# CPU.net
KiCad netlist of a schematic drawn in Altium Designer
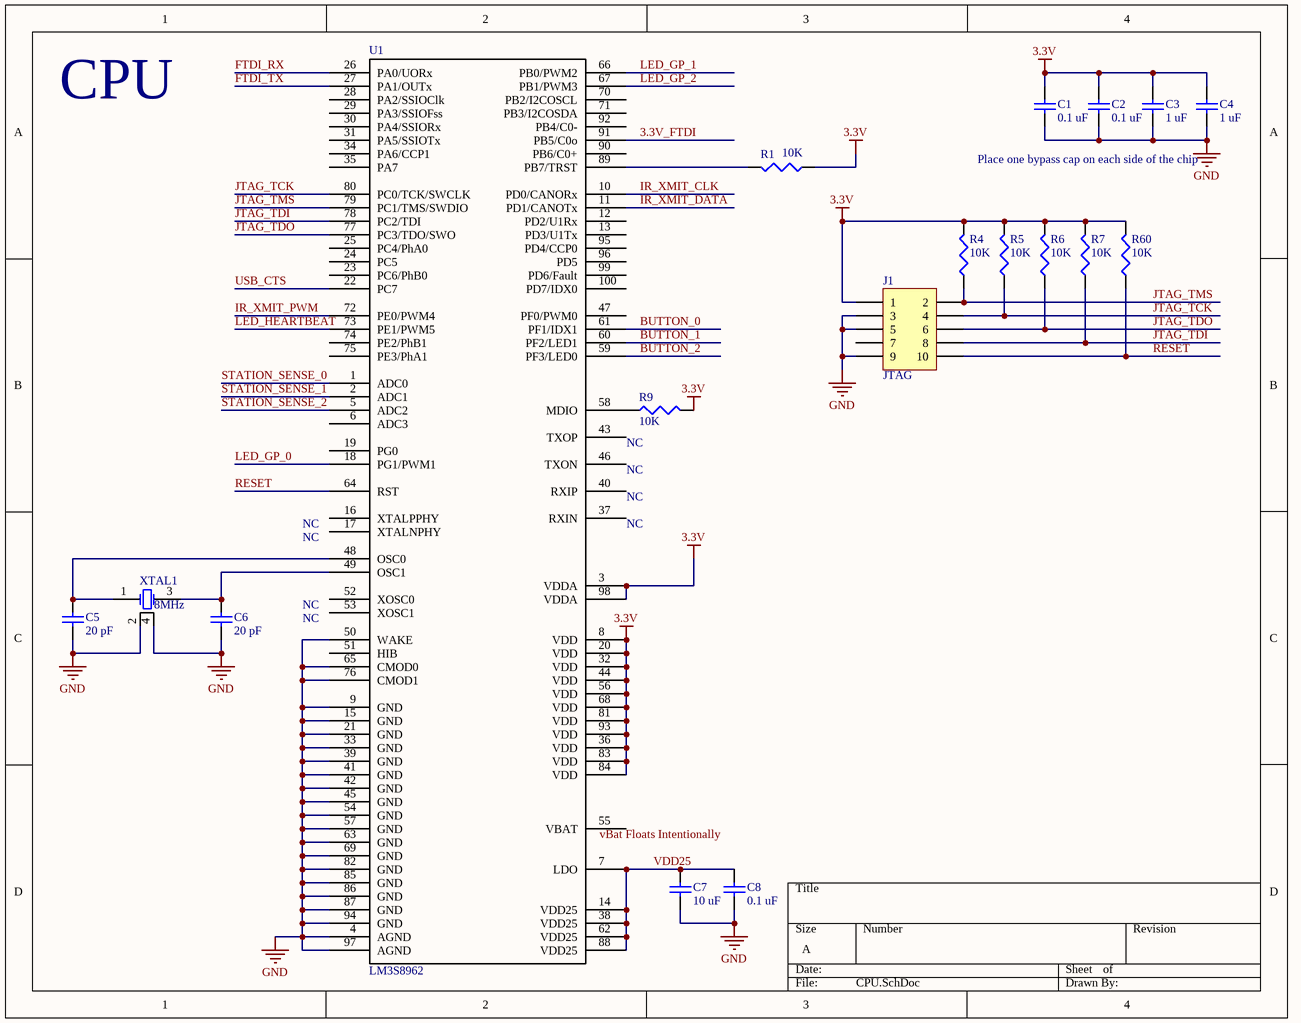
[diagram p0: CPU.SchDoc]

(export (version "E")
  (design (tool "Eeschema 10.0.6"))
  (components
    (comp (ref "C1")
      (value "0.1 uF")
      (footprint "CAPC1005L")
      (description "Capacitor")
      (fields (field (name "PUBLISHER") "Altium Limited"))
      (libsource (lib "mrone") (part "Cap"))
    )
    (comp (ref "C2")
      (value "0.1 uF")
      (footprint "CAPC1005L")
      (description "Capacitor")
      (fields (field (name "PUBLISHER") "Altium Limited"))
      (libsource (lib "mrone") (part "Cap"))
    )
    (comp (ref "C3")
      (value "1 uF")
      (footprint "CAPC1608L")
      (description "Capacitor")
      (fields (field (name "PUBLISHER") "Altium Limited"))
      (libsource (lib "mrone") (part "Cap"))
    )
    (comp (ref "C4")
      (value "1 uF")
      (footprint "CAPC1608L")
      (description "Capacitor")
      (fields (field (name "PUBLISHER") "Altium Limited"))
      (libsource (lib "mrone") (part "Cap"))
    )
    (comp (ref "C5")
      (value "20 pF")
      (footprint "CAPC1005L")
      (description "Capacitor")
      (fields (field (name "PUBLISHER") "Altium Limited"))
      (libsource (lib "mrone") (part "Cap"))
    )
    (comp (ref "C6")
      (value "20 pF")
      (footprint "CAPC1005L")
      (description "Capacitor")
      (fields (field (name "PUBLISHER") "Altium Limited"))
      (libsource (lib "mrone") (part "Cap"))
    )
    (comp (ref "C7")
      (value "10 uF")
      (footprint "CAPC1608L")
      (description "Capacitor")
      (fields (field (name "PUBLISHER") "Altium Limited"))
      (libsource (lib "mrone") (part "Cap"))
    )
    (comp (ref "C8")
      (value "0.1 uF")
      (footprint "CAPC1005L")
      (description "Capacitor")
      (fields (field (name "PUBLISHER") "Altium Limited"))
      (libsource (lib "mrone") (part "Cap"))
    )
    (comp (ref "J1")
      (value "JTAG")
      (footprint "JTAG-10")
      (description "Header, 5-Pin, Dual row, Right Angle")
      (fields (field (name "PUBLISHER") "Altium Limited"))
      (libsource (lib "Miscellaneous Connectors") (part "Header 5X2H"))
    )
    (comp (ref "R1")
      (value "10K")
      (footprint "RESC1608L")
      (description "Resistor")
      (fields (field (name "Comment") "Res3") (field (name "PUBLISHER") "Altium Limited"))
      (libsource (lib "Miscellaneous Devices") (part "Res3"))
    )
    (comp (ref "R4")
      (value "10K")
      (footprint "RESC1608L")
      (description "Resistor")
      (fields (field (name "Comment") "Res3") (field (name "PUBLISHER") "Altium Limited"))
      (libsource (lib "Miscellaneous Devices") (part "Res3"))
    )
    (comp (ref "R5")
      (value "10K")
      (footprint "RESC1608L")
      (description "Resistor")
      (fields (field (name "Comment") "Res3") (field (name "PUBLISHER") "Altium Limited"))
      (libsource (lib "Miscellaneous Devices") (part "Res3"))
    )
    (comp (ref "R6")
      (value "10K")
      (footprint "RESC1608L")
      (description "Resistor")
      (fields (field (name "Comment") "Res3") (field (name "PUBLISHER") "Altium Limited"))
      (libsource (lib "Miscellaneous Devices") (part "Res3"))
    )
    (comp (ref "R7")
      (value "10K")
      (footprint "RESC1608L")
      (description "Resistor")
      (fields (field (name "Comment") "Res3") (field (name "PUBLISHER") "Altium Limited"))
      (libsource (lib "Miscellaneous Devices") (part "Res3"))
    )
    (comp (ref "R9")
      (value "10K")
      (footprint "RESC1608L")
      (description "Resistor")
      (fields (field (name "Comment") "Res3") (field (name "PUBLISHER") "Altium Limited"))
      (libsource (lib "Miscellaneous Devices") (part "Res3"))
    )
    (comp (ref "R60")
      (value "10K")
      (footprint "RESC1608L")
      (description "Resistor")
      (fields (field (name "Comment") "Res3") (field (name "PUBLISHER") "Altium Limited"))
      (libsource (lib "Miscellaneous Devices") (part "Res3"))
    )
    (comp (ref "U1")
      (value "LM3S8962")
      (footprint "LQFP-100")
      (libsource (lib "Schematic Components") (part "LM3S8962"))
    )
    (comp (ref "XTAL1") (value "8MHz") (footprint "CRYSTAL") (libsource (lib "mrone") (part "Crystal")))
  )
  (nets
    (net (code "1") (name "/3.3V_FTDI") (class "Default")
      (node (ref "U1") (pin "91") (pinfunction "PB5/C0o_91") (pintype "passive"))
    )
    (net (code "2") (name "/BUTTON_0") (class "Default")
      (node (ref "U1") (pin "61") (pinfunction "PF1/IDX1_61") (pintype "passive"))
    )
    (net (code "3") (name "/BUTTON_1") (class "Default")
      (node (ref "U1") (pin "60") (pinfunction "PF2/LED1_60") (pintype "passive"))
    )
    (net (code "4") (name "/BUTTON_2") (class "Default")
      (node (ref "U1") (pin "59") (pinfunction "PF3/LED0_59") (pintype "passive"))
    )
    (net (code "5") (name "/FTDI_RX") (class "Default")
      (node (ref "U1") (pin "26") (pinfunction "PA0/UORx_26") (pintype "passive"))
    )
    (net (code "6") (name "/FTDI_TX") (class "Default")
      (node (ref "U1") (pin "27") (pinfunction "PA1/OUTx_27") (pintype "passive"))
    )
    (net (code "7") (name "/IR_XMIT_CLK") (class "Default")
      (node (ref "U1") (pin "10") (pinfunction "PD0/CANORx_10") (pintype "passive"))
    )
    (net (code "8") (name "/IR_XMIT_DATA") (class "Default")
      (node (ref "U1") (pin "11") (pinfunction "PD1/CANOTx_11") (pintype "passive"))
    )
    (net (code "9") (name "/IR_XMIT_PWM") (class "Default")
      (node (ref "U1") (pin "72") (pinfunction "PE0/PWM4_72") (pintype "passive"))
    )
    (net (code "10") (name "/JTAG_TCK") (class "Default")
      (node (ref "J1") (pin "4") (pinfunction "4_4") (pintype "passive"))
      (node (ref "R5") (pin "1") (pinfunction "1_1") (pintype "passive"))
      (node (ref "U1") (pin "80") (pinfunction "PC0/TCK/SWCLK_80") (pintype "passive"))
    )
    (net (code "11") (name "/JTAG_TDI") (class "Default")
      (node (ref "J1") (pin "8") (pinfunction "8_8") (pintype "passive"))
      (node (ref "R7") (pin "1") (pinfunction "1_1") (pintype "passive"))
      (node (ref "U1") (pin "78") (pinfunction "PC2/TDI_78") (pintype "passive"))
    )
    (net (code "12") (name "/JTAG_TDO") (class "Default")
      (node (ref "J1") (pin "6") (pinfunction "6_6") (pintype "passive"))
      (node (ref "R6") (pin "1") (pinfunction "1_1") (pintype "passive"))
      (node (ref "U1") (pin "77") (pinfunction "PC3/TDO/SWO_77") (pintype "passive"))
    )
    (net (code "13") (name "/JTAG_TMS") (class "Default")
      (node (ref "J1") (pin "2") (pinfunction "2_2") (pintype "passive"))
      (node (ref "R4") (pin "1") (pinfunction "1_1") (pintype "passive"))
      (node (ref "U1") (pin "79") (pinfunction "PC1/TMS/SWDIO_79") (pintype "passive"))
    )
    (net (code "14") (name "/LED_GP_0") (class "Default")
      (node (ref "U1") (pin "18") (pinfunction "PG1/PWM1_18") (pintype "passive"))
    )
    (net (code "15") (name "/LED_GP_1") (class "Default")
      (node (ref "U1") (pin "66") (pinfunction "PB0/PWM2_66") (pintype "passive"))
    )
    (net (code "16") (name "/LED_GP_2") (class "Default")
      (node (ref "U1") (pin "67") (pinfunction "PB1/PWM3_67") (pintype "passive"))
    )
    (net (code "17") (name "/LED_HEARTBEAT") (class "Default")
      (node (ref "U1") (pin "73") (pinfunction "PE1/PWM5_73") (pintype "passive"))
    )
    (net (code "18") (name "/RESET") (class "Default")
      (node (ref "J1") (pin "10") (pinfunction "10_10") (pintype "passive"))
      (node (ref "R60") (pin "1") (pinfunction "1_1") (pintype "passive"))
      (node (ref "U1") (pin "64") (pinfunction "RST_64") (pintype "passive"))
    )
    (net (code "19") (name "/STATION_SENSE_0") (class "Default")
      (node (ref "U1") (pin "1") (pinfunction "ADC0_1") (pintype "passive"))
    )
    (net (code "20") (name "/STATION_SENSE_1") (class "Default")
      (node (ref "U1") (pin "2") (pinfunction "ADC1_2") (pintype "passive"))
    )
    (net (code "21") (name "/STATION_SENSE_2") (class "Default")
      (node (ref "U1") (pin "5") (pinfunction "ADC2_5") (pintype "passive"))
    )
    (net (code "22") (name "/USB_CTS") (class "Default")
      (node (ref "U1") (pin "22") (pinfunction "PC7_22") (pintype "passive"))
    )
    (net (code "23") (name "/VDD25") (class "Default")
      (node (ref "C7") (pin "2") (pinfunction "2_2") (pintype "passive"))
      (node (ref "C8") (pin "2") (pinfunction "2_2") (pintype "passive"))
      (node (ref "U1") (pin "14") (pinfunction "VDD25_14") (pintype "passive"))
      (node (ref "U1") (pin "38") (pinfunction "VDD25_38") (pintype "passive"))
      (node (ref "U1") (pin "62") (pinfunction "VDD25_62") (pintype "passive"))
      (node (ref "U1") (pin "7") (pinfunction "LDO_7") (pintype "passive"))
      (node (ref "U1") (pin "88") (pinfunction "VDD25_88") (pintype "passive"))
    )
    (net (code "24") (name "3.3V") (class "Default")
      (node (ref "C1") (pin "2") (pinfunction "2_2") (pintype "passive"))
      (node (ref "C2") (pin "2") (pinfunction "2_2") (pintype "passive"))
      (node (ref "C3") (pin "2") (pinfunction "2_2") (pintype "passive"))
      (node (ref "C4") (pin "2") (pinfunction "2_2") (pintype "passive"))
      (node (ref "J1") (pin "1") (pinfunction "1_1") (pintype "passive"))
      (node (ref "R1") (pin "1") (pinfunction "1_1") (pintype "passive"))
      (node (ref "R4") (pin "2") (pinfunction "2_2") (pintype "passive"))
      (node (ref "R5") (pin "2") (pinfunction "2_2") (pintype "passive"))
      (node (ref "R6") (pin "2") (pinfunction "2_2") (pintype "passive"))
      (node (ref "R60") (pin "2") (pinfunction "2_2") (pintype "passive"))
      (node (ref "R7") (pin "2") (pinfunction "2_2") (pintype "passive"))
      (node (ref "R9") (pin "2") (pinfunction "2_2") (pintype "passive"))
      (node (ref "U1") (pin "20") (pinfunction "VDD_20") (pintype "passive"))
      (node (ref "U1") (pin "3") (pinfunction "VDDA_3") (pintype "passive"))
      (node (ref "U1") (pin "32") (pinfunction "VDD_32") (pintype "passive"))
      (node (ref "U1") (pin "36") (pinfunction "VDD_36") (pintype "passive"))
      (node (ref "U1") (pin "44") (pinfunction "VDD_44") (pintype "passive"))
      (node (ref "U1") (pin "56") (pinfunction "VDD_56") (pintype "passive"))
      (node (ref "U1") (pin "68") (pinfunction "VDD_68") (pintype "passive"))
      (node (ref "U1") (pin "8") (pinfunction "VDD_8") (pintype "passive"))
      (node (ref "U1") (pin "81") (pinfunction "VDD_81") (pintype "passive"))
      (node (ref "U1") (pin "83") (pinfunction "VDD_83") (pintype "passive"))
      (node (ref "U1") (pin "84") (pinfunction "VDD_84") (pintype "passive"))
      (node (ref "U1") (pin "93") (pinfunction "VDD_93") (pintype "passive"))
      (node (ref "U1") (pin "98") (pinfunction "VDDA_98") (pintype "passive"))
    )
    (net (code "25") (name "GND") (class "Default")
      (node (ref "C1") (pin "1") (pinfunction "1_1") (pintype "passive"))
      (node (ref "C2") (pin "1") (pinfunction "1_1") (pintype "passive"))
      (node (ref "C3") (pin "1") (pinfunction "1_1") (pintype "passive"))
      (node (ref "C4") (pin "1") (pinfunction "1_1") (pintype "passive"))
      (node (ref "C5") (pin "1") (pinfunction "1_1") (pintype "passive"))
      (node (ref "C6") (pin "1") (pinfunction "1_1") (pintype "passive"))
      (node (ref "C7") (pin "1") (pinfunction "1_1") (pintype "passive"))
      (node (ref "C8") (pin "1") (pinfunction "1_1") (pintype "passive"))
      (node (ref "J1") (pin "3") (pinfunction "3_3") (pintype "passive"))
      (node (ref "J1") (pin "5") (pinfunction "5_5") (pintype "passive"))
      (node (ref "J1") (pin "9") (pinfunction "9_9") (pintype "passive"))
      (node (ref "U1") (pin "15") (pinfunction "GND_15") (pintype "passive"))
      (node (ref "U1") (pin "21") (pinfunction "GND_21") (pintype "passive"))
      (node (ref "U1") (pin "33") (pinfunction "GND_33") (pintype "passive"))
      (node (ref "U1") (pin "39") (pinfunction "GND_39") (pintype "passive"))
      (node (ref "U1") (pin "4") (pinfunction "AGND_4") (pintype "passive"))
      (node (ref "U1") (pin "41") (pinfunction "GND_41") (pintype "passive"))
      (node (ref "U1") (pin "42") (pinfunction "GND_42") (pintype "passive"))
      (node (ref "U1") (pin "45") (pinfunction "GND_45") (pintype "passive"))
      (node (ref "U1") (pin "50") (pinfunction "WAKE_50") (pintype "passive"))
      (node (ref "U1") (pin "54") (pinfunction "GND_54") (pintype "passive"))
      (node (ref "U1") (pin "57") (pinfunction "GND_57") (pintype "passive"))
      (node (ref "U1") (pin "63") (pinfunction "GND_63") (pintype "passive"))
      (node (ref "U1") (pin "65") (pinfunction "CMOD0_65") (pintype "passive"))
      (node (ref "U1") (pin "69") (pinfunction "GND_69") (pintype "passive"))
      (node (ref "U1") (pin "76") (pinfunction "CMOD1_76") (pintype "passive"))
      (node (ref "U1") (pin "82") (pinfunction "GND_82") (pintype "passive"))
      (node (ref "U1") (pin "85") (pinfunction "GND_85") (pintype "passive"))
      (node (ref "U1") (pin "86") (pinfunction "GND_86") (pintype "passive"))
      (node (ref "U1") (pin "87") (pinfunction "GND_87") (pintype "passive"))
      (node (ref "U1") (pin "9") (pinfunction "GND_9") (pintype "passive"))
      (node (ref "U1") (pin "94") (pinfunction "GND_94") (pintype "passive"))
      (node (ref "U1") (pin "97") (pinfunction "AGND_97") (pintype "passive"))
      (node (ref "XTAL1") (pin "2") (pinfunction "GND_2") (pintype "passive"))
      (node (ref "XTAL1") (pin "4") (pinfunction "GND_4") (pintype "passive"))
    )
    (net (code "26") (name "Net-(U1-MDIO)") (class "Default")
      (node (ref "R9") (pin "1") (pinfunction "1_1") (pintype "passive"))
      (node (ref "U1") (pin "58") (pinfunction "MDIO_58") (pintype "passive"))
    )
    (net (code "27") (name "Net-(U1-OSC0)") (class "Default")
      (node (ref "C5") (pin "2") (pinfunction "2_2") (pintype "passive"))
      (node (ref "U1") (pin "48") (pinfunction "OSC0_48") (pintype "passive"))
      (node (ref "XTAL1") (pin "1") (pinfunction "OSC1_1") (pintype "passive"))
    )
    (net (code "28") (name "Net-(U1-OSC1)") (class "Default")
      (node (ref "C6") (pin "2") (pinfunction "2_2") (pintype "passive"))
      (node (ref "U1") (pin "49") (pinfunction "OSC1_49") (pintype "passive"))
      (node (ref "XTAL1") (pin "3") (pinfunction "OSC2_3") (pintype "passive"))
    )
    (net (code "29") (name "Net-(U1-PB7{slash}TRST)") (class "Default")
      (node (ref "R1") (pin "2") (pinfunction "2_2") (pintype "passive"))
      (node (ref "U1") (pin "89") (pinfunction "PB7/TRST_89") (pintype "passive"))
    )
    (net (code "30") (name "unconnected-(J1-Pad7)") (class "Default")
      (node (ref "J1") (pin "7") (pinfunction "7_7") (pintype "passive"))
    )
    (net (code "31") (name "unconnected-(U1-ADC3-Pad6)") (class "Default")
      (node (ref "U1") (pin "6") (pinfunction "ADC3_6") (pintype "passive"))
    )
    (net (code "32") (name "unconnected-(U1-HIB-Pad51)") (class "Default")
      (node (ref "U1") (pin "51") (pinfunction "HIB_51") (pintype "passive"))
    )
    (net (code "33") (name "unconnected-(U1-PA2{slash}SSIOClk-Pad28)") (class "Default")
      (node (ref "U1") (pin "28") (pinfunction "PA2/SSIOClk_28") (pintype "passive"))
    )
    (net (code "34") (name "unconnected-(U1-PA3{slash}SSIOFss-Pad29)") (class "Default")
      (node (ref "U1") (pin "29") (pinfunction "PA3/SSIOFss_29") (pintype "passive"))
    )
    (net (code "35") (name "unconnected-(U1-PA4{slash}SSIORx-Pad30)") (class "Default")
      (node (ref "U1") (pin "30") (pinfunction "PA4/SSIORx_30") (pintype "passive"))
    )
    (net (code "36") (name "unconnected-(U1-PA5{slash}SSIOTx-Pad31)") (class "Default")
      (node (ref "U1") (pin "31") (pinfunction "PA5/SSIOTx_31") (pintype "passive"))
    )
    (net (code "37") (name "unconnected-(U1-PA6{slash}CCP1-Pad34)") (class "Default")
      (node (ref "U1") (pin "34") (pinfunction "PA6/CCP1_34") (pintype "passive"))
    )
    (net (code "38") (name "unconnected-(U1-PA7-Pad35)") (class "Default")
      (node (ref "U1") (pin "35") (pinfunction "PA7_35") (pintype "passive"))
    )
    (net (code "39") (name "unconnected-(U1-PB2{slash}I2COSCL-Pad70)") (class "Default")
      (node (ref "U1") (pin "70") (pinfunction "PB2/I2COSCL_70") (pintype "passive"))
    )
    (net (code "40") (name "unconnected-(U1-PB3{slash}I2COSDA-Pad71)") (class "Default")
      (node (ref "U1") (pin "71") (pinfunction "PB3/I2COSDA_71") (pintype "passive"))
    )
    (net (code "41") (name "unconnected-(U1-PB4{slash}C0--Pad92)") (class "Default")
      (node (ref "U1") (pin "92") (pinfunction "PB4/C0-_92") (pintype "passive"))
    )
    (net (code "42") (name "unconnected-(U1-PB6{slash}C0+-Pad90)") (class "Default")
      (node (ref "U1") (pin "90") (pinfunction "PB6/C0+_90") (pintype "passive"))
    )
    (net (code "43") (name "unconnected-(U1-PC4{slash}PhA0-Pad25)") (class "Default")
      (node (ref "U1") (pin "25") (pinfunction "PC4/PhA0_25") (pintype "passive"))
    )
    (net (code "44") (name "unconnected-(U1-PC5-Pad24)") (class "Default")
      (node (ref "U1") (pin "24") (pinfunction "PC5_24") (pintype "passive"))
    )
    (net (code "45") (name "unconnected-(U1-PC6{slash}PhB0-Pad23)") (class "Default")
      (node (ref "U1") (pin "23") (pinfunction "PC6/PhB0_23") (pintype "passive"))
    )
    (net (code "46") (name "unconnected-(U1-PD2{slash}U1Rx-Pad12)") (class "Default")
      (node (ref "U1") (pin "12") (pinfunction "PD2/U1Rx_12") (pintype "passive"))
    )
    (net (code "47") (name "unconnected-(U1-PD3{slash}U1Tx-Pad13)") (class "Default")
      (node (ref "U1") (pin "13") (pinfunction "PD3/U1Tx_13") (pintype "passive"))
    )
    (net (code "48") (name "unconnected-(U1-PD4{slash}CCP0-Pad95)") (class "Default")
      (node (ref "U1") (pin "95") (pinfunction "PD4/CCP0_95") (pintype "passive"))
    )
    (net (code "49") (name "unconnected-(U1-PD5-Pad96)") (class "Default")
      (node (ref "U1") (pin "96") (pinfunction "PD5_96") (pintype "passive"))
    )
    (net (code "50") (name "unconnected-(U1-PD6{slash}Fault-Pad99)") (class "Default")
      (node (ref "U1") (pin "99") (pinfunction "PD6/Fault_99") (pintype "passive"))
    )
    (net (code "51") (name "unconnected-(U1-PD7{slash}IDX0-Pad100)") (class "Default")
      (node (ref "U1") (pin "100") (pinfunction "PD7/IDX0_100") (pintype "passive"))
    )
    (net (code "52") (name "unconnected-(U1-PE2{slash}PhB1-Pad74)") (class "Default")
      (node (ref "U1") (pin "74") (pinfunction "PE2/PhB1_74") (pintype "passive"))
    )
    (net (code "53") (name "unconnected-(U1-PE3{slash}PhA1-Pad75)") (class "Default")
      (node (ref "U1") (pin "75") (pinfunction "PE3/PhA1_75") (pintype "passive"))
    )
    (net (code "54") (name "unconnected-(U1-PF0{slash}PWM0-Pad47)") (class "Default")
      (node (ref "U1") (pin "47") (pinfunction "PF0/PWM0_47") (pintype "passive"))
    )
    (net (code "55") (name "unconnected-(U1-PG0-Pad19)") (class "Default")
      (node (ref "U1") (pin "19") (pinfunction "PG0_19") (pintype "passive"))
    )
    (net (code "56") (name "unconnected-(U1-RXIN-Pad37)") (class "Default")
      (node (ref "U1") (pin "37") (pinfunction "RXIN_37") (pintype "passive"))
    )
    (net (code "57") (name "unconnected-(U1-RXIP-Pad40)") (class "Default")
      (node (ref "U1") (pin "40") (pinfunction "RXIP_40") (pintype "passive"))
    )
    (net (code "58") (name "unconnected-(U1-TXON-Pad46)") (class "Default")
      (node (ref "U1") (pin "46") (pinfunction "TXON_46") (pintype "passive"))
    )
    (net (code "59") (name "unconnected-(U1-TXOP-Pad43)") (class "Default")
      (node (ref "U1") (pin "43") (pinfunction "TXOP_43") (pintype "passive"))
    )
    (net (code "60") (name "unconnected-(U1-VBAT-Pad55)") (class "Default")
      (node (ref "U1") (pin "55") (pinfunction "VBAT_55") (pintype "passive"))
    )
    (net (code "61") (name "unconnected-(U1-XOSC0-Pad52)") (class "Default")
      (node (ref "U1") (pin "52") (pinfunction "XOSC0_52") (pintype "passive"))
    )
    (net (code "62") (name "unconnected-(U1-XOSC1-Pad53)") (class "Default")
      (node (ref "U1") (pin "53") (pinfunction "XOSC1_53") (pintype "passive"))
    )
    (net (code "63") (name "unconnected-(U1-XTALNPHY-Pad17)") (class "Default")
      (node (ref "U1") (pin "17") (pinfunction "XTALNPHY_17") (pintype "passive"))
    )
    (net (code "64") (name "unconnected-(U1-XTALPPHY-Pad16)") (class "Default")
      (node (ref "U1") (pin "16") (pinfunction "XTALPPHY_16") (pintype "passive"))
    )
  )
)
